# T1L_PHY.net
KiCad netlist of a schematic drawn in Altium Designer
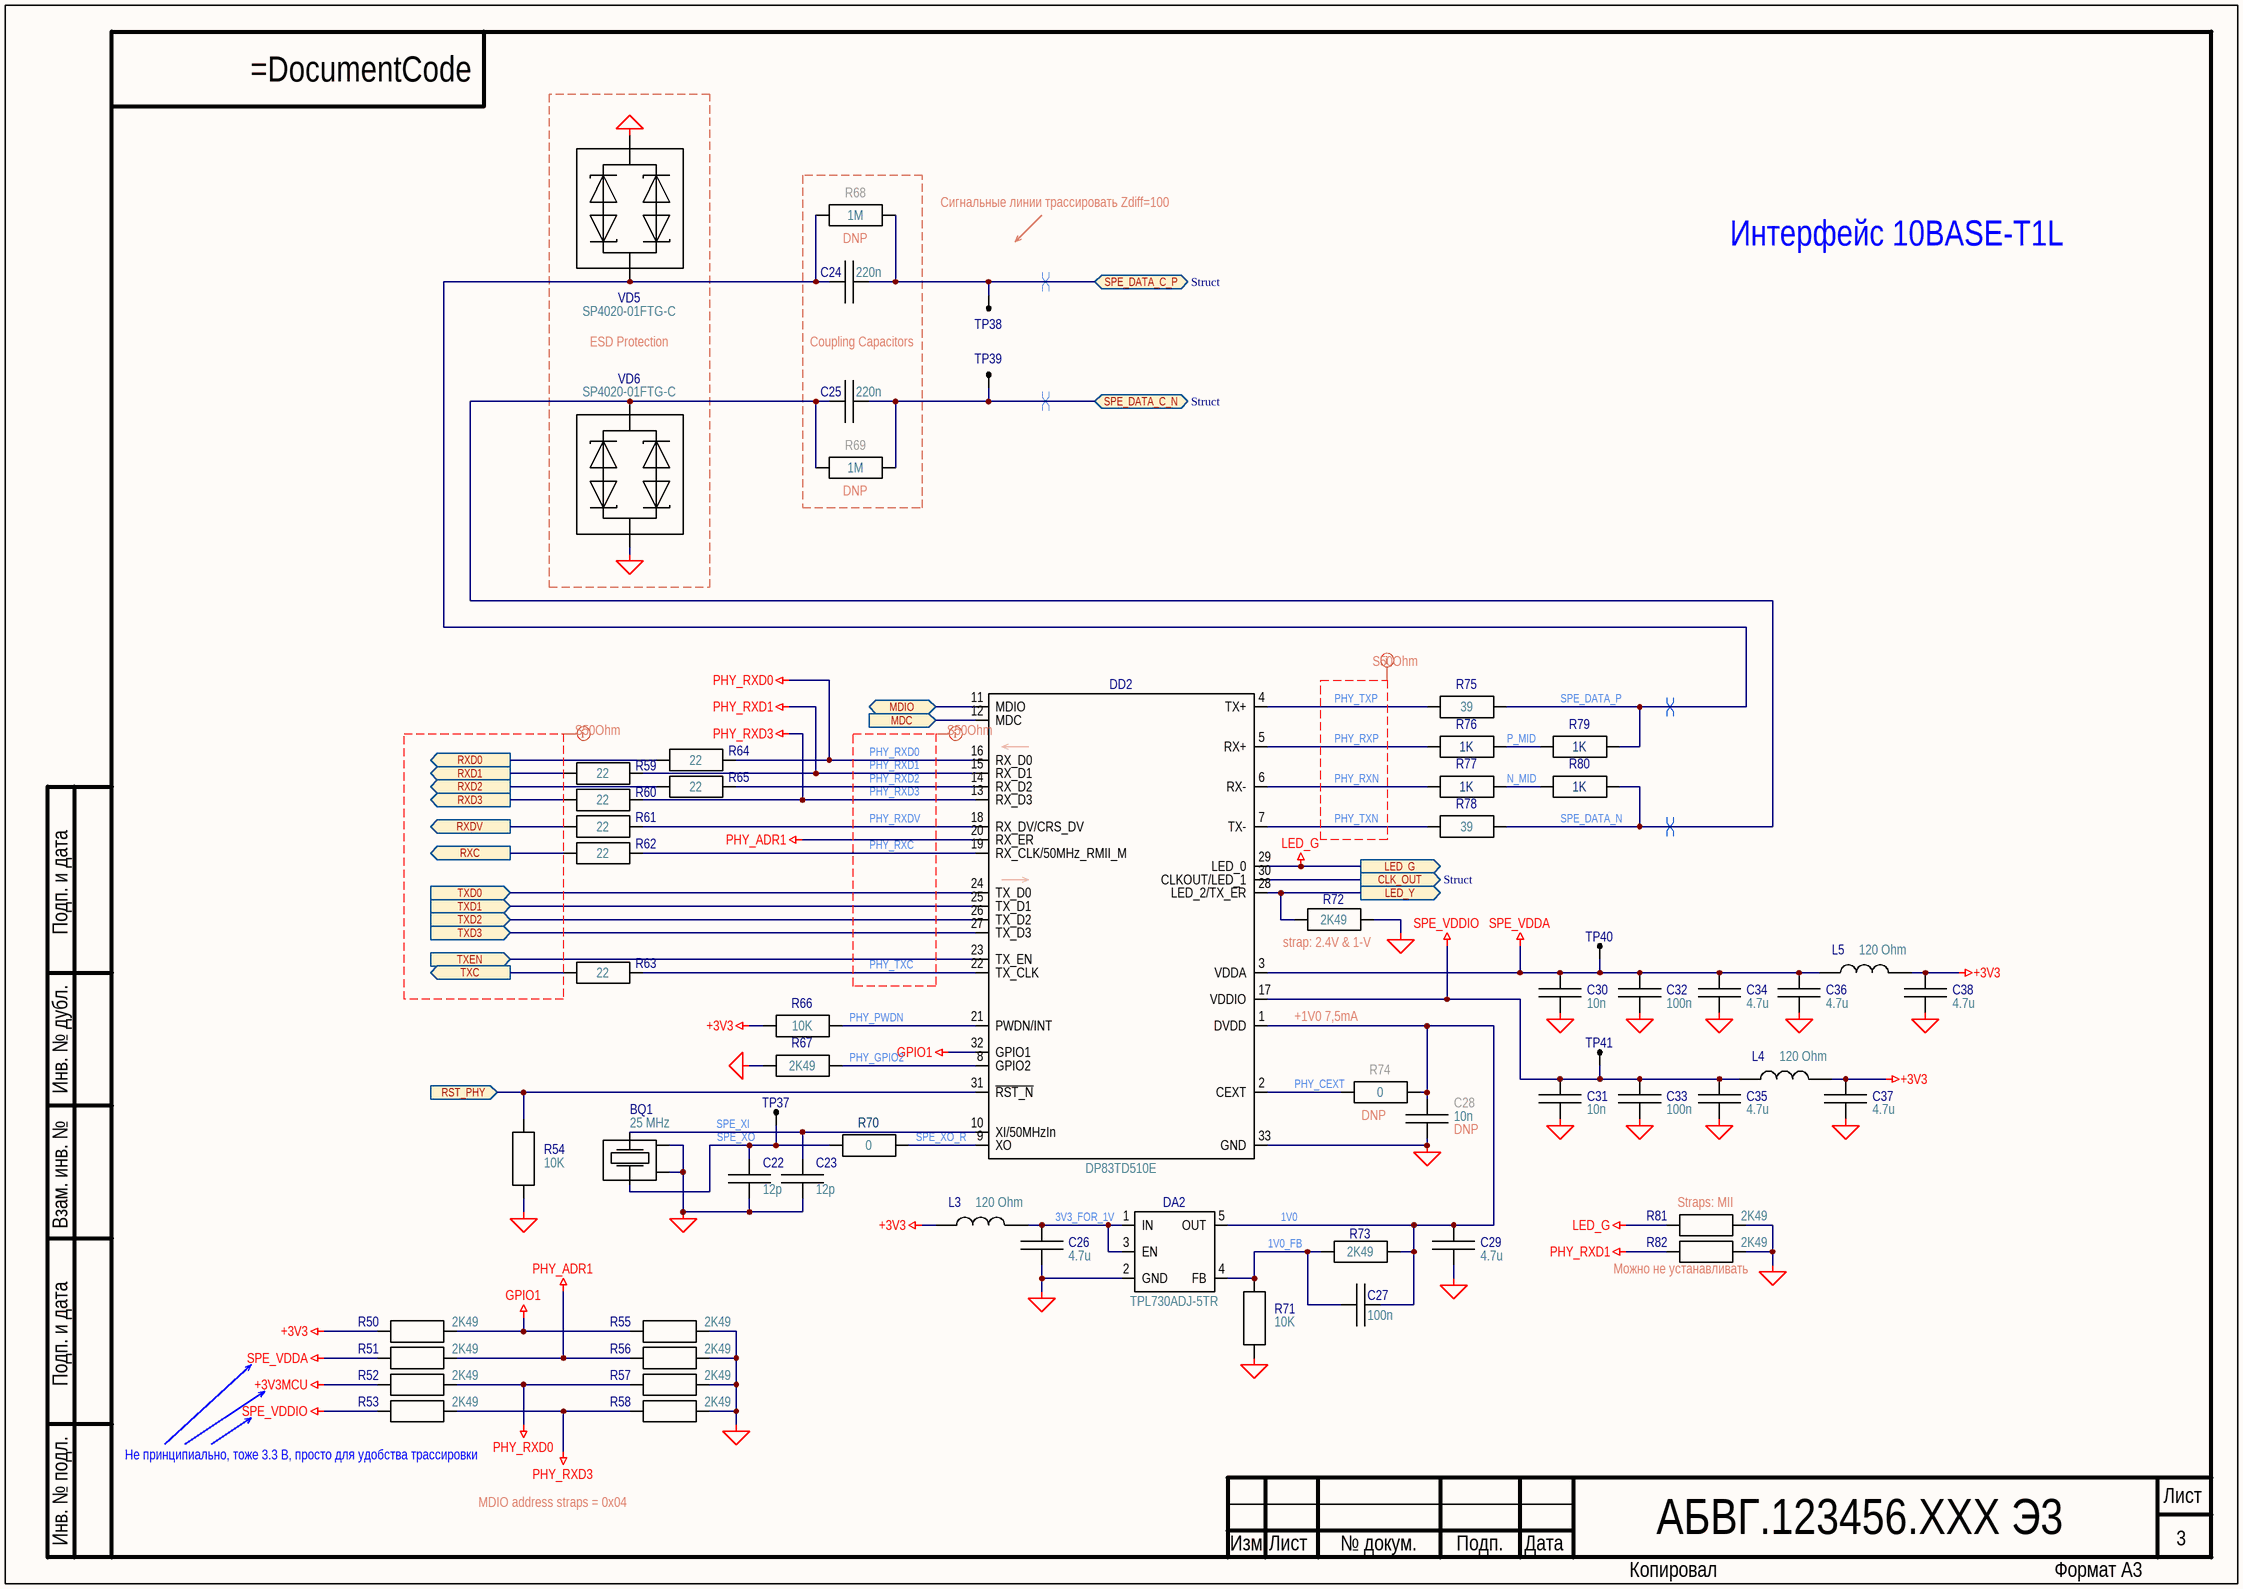
[diagram p0: T1L_PHY.SchDoc]

(export (version "E")
  (design (tool "Eeschema 10.0.6"))
  (components
    (comp (ref "BQ1")
      (value "25 MHz")
      (footprint "DSX321G_under12MHz")
      (description "Резонатор кварцевый X322525MOB4SI 25 MHz")
      (fields (field (name "MANUFACTURER PART NUMBER") "X322525MOB4SI") (field (name "MANUFACTURER") "YXC"))
      (libsource (lib "ums") (part "YSX321SL"))
    )
    (comp (ref "C22")
      (value "12p")
      (footprint "C0603")
      (description "Чип-конденсатор 12 пФ 5% 50 В C0G(NP0) 0603")
      (fields
        (field (name "MANUFACTURER PART NUMBER") "CC0603JRNPO9BN120")
        (field (name "MANUFACTURER") "Yageo")
      )
      (libsource (lib "ums") (part "C0603"))
    )
    (comp (ref "C23")
      (value "12p")
      (footprint "C0603")
      (description "Чип-конденсатор 12 пФ 5% 50 В C0G(NP0) 0603")
      (fields
        (field (name "MANUFACTURER PART NUMBER") "CC0603JRNPO9BN120")
        (field (name "MANUFACTURER") "Yageo")
      )
      (libsource (lib "ums") (part "C0603"))
    )
    (comp (ref "C24")
      (value "220n")
      (footprint "C0805_rounded")
      (description "Чип-конденсатор 0,22 мкФ ±10% 100 В X7R 0805")
      (fields
        (field (name "MANUFACTURER PART NUMBER") "CC0805KKX7R0BB224")
        (field (name "MANUFACTURER") "Yageo")
      )
      (libsource (lib "ums") (part "C0805_2"))
    )
    (comp (ref "C25")
      (value "220n")
      (footprint "C0805_rounded")
      (description "Чип-конденсатор 0,22 мкФ ±10% 100 В X7R 0805")
      (fields
        (field (name "MANUFACTURER PART NUMBER") "CC0805KKX7R0BB224")
        (field (name "MANUFACTURER") "Yageo")
      )
      (libsource (lib "ums") (part "C0805_2"))
    )
    (comp (ref "C26")
      (value "4.7u")
      (footprint "C0603")
      (description "Чип-конденсатор 4,7 мкФ 10% 16 В X5R 0603")
      (fields
        (field (name "MANUFACTURER PART NUMBER") "CC0603KRX5R7BB475")
        (field (name "MANUFACTURER") "Yageo")
      )
      (libsource (lib "ums") (part "C0603"))
    )
    (comp (ref "C27")
      (value "100n")
      (footprint "C0402")
      (description "Чип-конденсатор 100 нФ 10% 50 В X7R 0402")
      (fields
        (field (name "MANUFACTURER PART NUMBER") "CC0402KRX7R9BB104")
        (field (name "MANUFACTURER") "Yageo")
      )
      (libsource (lib "ums") (part "C0402"))
    )
    (comp (ref "C28")
      (value "10n")
      (footprint "C0402")
      (description "Чип-конденсатор 10 нФ 10% 50 В X7R 0402")
      (fields
        (field (name "MANUFACTURER PART NUMBER") "CC0402KRX7R9BB103")
        (field (name "MANUFACTURER") "Yageo")
      )
      (libsource (lib "ums") (part "C0402"))
    )
    (comp (ref "C29")
      (value "4.7u")
      (footprint "C0603")
      (description "Чип-конденсатор 4,7 мкФ 10% 16 В X5R 0603")
      (fields
        (field (name "MANUFACTURER PART NUMBER") "CC0603KRX5R7BB475")
        (field (name "MANUFACTURER") "Yageo")
      )
      (libsource (lib "ums") (part "C0603"))
    )
    (comp (ref "C30")
      (value "10n")
      (footprint "C0402")
      (description "Чип-конденсатор 10 нФ 10% 50 В X7R 0402")
      (fields
        (field (name "MANUFACTURER PART NUMBER") "CC0402KRX7R9BB103")
        (field (name "MANUFACTURER") "Yageo")
      )
      (libsource (lib "ums") (part "C0402"))
    )
    (comp (ref "C31")
      (value "10n")
      (footprint "C0402")
      (description "Чип-конденсатор 10 нФ 10% 50 В X7R 0402")
      (fields
        (field (name "MANUFACTURER PART NUMBER") "CC0402KRX7R9BB103")
        (field (name "MANUFACTURER") "Yageo")
      )
      (libsource (lib "ums") (part "C0402"))
    )
    (comp (ref "C32")
      (value "100n")
      (footprint "C0402")
      (description "Чип-конденсатор 100 нФ 10% 50 В X7R 0402")
      (fields
        (field (name "MANUFACTURER PART NUMBER") "CC0402KRX7R9BB104")
        (field (name "MANUFACTURER") "Yageo")
      )
      (libsource (lib "ums") (part "C0402"))
    )
    (comp (ref "C33")
      (value "100n")
      (footprint "C0402")
      (description "Чип-конденсатор 100 нФ 10% 50 В X7R 0402")
      (fields
        (field (name "MANUFACTURER PART NUMBER") "CC0402KRX7R9BB104")
        (field (name "MANUFACTURER") "Yageo")
      )
      (libsource (lib "ums") (part "C0402"))
    )
    (comp (ref "C34")
      (value "4.7u")
      (footprint "C0603")
      (description "Чип-конденсатор 4,7 мкФ 10% 16 В X5R 0603")
      (fields
        (field (name "MANUFACTURER PART NUMBER") "CC0603KRX5R7BB475")
        (field (name "MANUFACTURER") "Yageo")
      )
      (libsource (lib "ums") (part "C0603"))
    )
    (comp (ref "C35")
      (value "4.7u")
      (footprint "C0603")
      (description "Чип-конденсатор 4,7 мкФ 10% 16 В X5R 0603")
      (fields
        (field (name "MANUFACTURER PART NUMBER") "CC0603KRX5R7BB475")
        (field (name "MANUFACTURER") "Yageo")
      )
      (libsource (lib "ums") (part "C0603"))
    )
    (comp (ref "C36")
      (value "4.7u")
      (footprint "C0603")
      (description "Чип-конденсатор 4,7 мкФ 10% 16 В X5R 0603")
      (fields
        (field (name "MANUFACTURER PART NUMBER") "CC0603KRX5R7BB475")
        (field (name "MANUFACTURER") "Yageo")
      )
      (libsource (lib "ums") (part "C0603"))
    )
    (comp (ref "C37")
      (value "4.7u")
      (footprint "C0603")
      (description "Чип-конденсатор 4,7 мкФ 10% 16 В X5R 0603")
      (fields
        (field (name "MANUFACTURER PART NUMBER") "CC0603KRX5R7BB475")
        (field (name "MANUFACTURER") "Yageo")
      )
      (libsource (lib "ums") (part "C0603"))
    )
    (comp (ref "C38")
      (value "4.7u")
      (footprint "C0603")
      (description "Чип-конденсатор 4,7 мкФ 10% 16 В X5R 0603")
      (fields
        (field (name "MANUFACTURER PART NUMBER") "CC0603KRX5R7BB475")
        (field (name "MANUFACTURER") "Yageo")
      )
      (libsource (lib "ums") (part "C0603"))
    )
    (comp (ref "DA2")
      (value "TPL730ADJ-5TR")
      (footprint "SOT-23(DBV5)")
      (description "LDO-регулятор SOT-23-5")
      (fields (field (name "MANUFACTURER") "3PEAK"))
      (libsource (lib "ums") (part "TPL730ADJ-5TR"))
    )
    (comp (ref "DD2")
      (value "DP83TD510E")
      (footprint "QFN-32_ePAD_2.1x2.1")
      (description "Микросхема приёмопередатчика 10Base-T1L")
      (fields
        (field (name "MANUFACTURER") "Texas Instruments")
        (field (name "MANUFACTURER PART NUMBER") "DP83TD510ERHB")
      )
      (libsource (lib "ums") (part "DP83TD510E"))
    )
    (comp (ref "L3")
      (value "120 Ohm")
      (footprint "BLM18PG")
      (description "Фильтр индуктивный 120 Ом @ 100 МГц 2 А 0603")
      (fields
        (field (name "MANUFACTURER") "FENGHUA Advanced Technology")
        (field (name "MANUFACTURER PART NUMBER") "CBM160808U121T")
      )
      (libsource (lib "ums") (part "BLM18PG121SN1D"))
    )
    (comp (ref "L4")
      (value "120 Ohm")
      (footprint "BLM18PG")
      (description "Фильтр индуктивный 120 Ом @ 100 МГц 2 А 0603")
      (fields
        (field (name "MANUFACTURER") "FENGHUA Advanced Technology")
        (field (name "MANUFACTURER PART NUMBER") "CBM160808U121T")
      )
      (libsource (lib "ums") (part "BLM18PG121SN1D"))
    )
    (comp (ref "L5")
      (value "120 Ohm")
      (footprint "BLM18PG")
      (description "Фильтр индуктивный 120 Ом @ 100 МГц 2 А 0603")
      (fields
        (field (name "MANUFACTURER") "FENGHUA Advanced Technology")
        (field (name "MANUFACTURER PART NUMBER") "CBM160808U121T")
      )
      (libsource (lib "ums") (part "BLM18PG121SN1D"))
    )
    (comp (ref "R50")
      (value "2K49")
      (footprint "R0402")
      (description "Чип-резистор 2,49 кОм 1% 0402")
      (fields
        (field (name "MANUFACTURER PART NUMBER") "RC0402FR-072K49L")
        (field (name "MANUFACTURER") "Yageo")
      )
      (libsource (lib "ums") (part "R0402_tooth_4"))
    )
    (comp (ref "R51")
      (value "2K49")
      (footprint "R0402")
      (description "Чип-резистор 2,49 кОм 1% 0402")
      (fields
        (field (name "MANUFACTURER PART NUMBER") "RC0402FR-072K49L")
        (field (name "MANUFACTURER") "Yageo")
      )
      (libsource (lib "ums") (part "R0402_tooth_4"))
    )
    (comp (ref "R52")
      (value "2K49")
      (footprint "R0402")
      (description "Чип-резистор 2,49 кОм 1% 0402")
      (fields
        (field (name "MANUFACTURER PART NUMBER") "RC0402FR-072K49L")
        (field (name "MANUFACTURER") "Yageo")
      )
      (libsource (lib "ums") (part "R0402_tooth_4"))
    )
    (comp (ref "R53")
      (value "2K49")
      (footprint "R0402")
      (description "Чип-резистор 2,49 кОм 1% 0402")
      (fields
        (field (name "MANUFACTURER PART NUMBER") "RC0402FR-072K49L")
        (field (name "MANUFACTURER") "Yageo")
      )
      (libsource (lib "ums") (part "R0402_tooth_4"))
    )
    (comp (ref "R54")
      (value "10K")
      (footprint "R0402")
      (description "Чип-резистор 10 кОм 1% 0402")
      (fields
        (field (name "MANUFACTURER PART NUMBER") "RC0402FR-0710KL")
        (field (name "MANUFACTURER") "Yageo")
      )
      (libsource (lib "ums") (part "R0402"))
    )
    (comp (ref "R55")
      (value "2K49")
      (footprint "R0402")
      (description "Чип-резистор 2,49 кОм 1% 0402")
      (fields
        (field (name "MANUFACTURER PART NUMBER") "RC0402FR-072K49L")
        (field (name "MANUFACTURER") "Yageo")
      )
      (libsource (lib "ums") (part "R0402_tooth_4"))
    )
    (comp (ref "R56")
      (value "2K49")
      (footprint "R0402")
      (description "Чип-резистор 2,49 кОм 1% 0402")
      (fields
        (field (name "MANUFACTURER PART NUMBER") "RC0402FR-072K49L")
        (field (name "MANUFACTURER") "Yageo")
      )
      (libsource (lib "ums") (part "R0402_tooth_4"))
    )
    (comp (ref "R57")
      (value "2K49")
      (footprint "R0402")
      (description "Чип-резистор 2,49 кОм 1% 0402")
      (fields
        (field (name "MANUFACTURER PART NUMBER") "RC0402FR-072K49L")
        (field (name "MANUFACTURER") "Yageo")
      )
      (libsource (lib "ums") (part "R0402_tooth_4"))
    )
    (comp (ref "R58")
      (value "2K49")
      (footprint "R0402")
      (description "Чип-резистор 2,49 кОм 1% 0402")
      (fields
        (field (name "MANUFACTURER PART NUMBER") "RC0402FR-072K49L")
        (field (name "MANUFACTURER") "Yageo")
      )
      (libsource (lib "ums") (part "R0402_tooth_4"))
    )
    (comp (ref "R59")
      (value "22")
      (footprint "R0402")
      (description "Чип-резистор 22 Ом 1% 0402")
      (fields
        (field (name "MANUFACTURER PART NUMBER") "RC0402FR-0722RL")
        (field (name "MANUFACTURER") "Yageo")
      )
      (libsource (lib "ums") (part "R0402_tooth_1"))
    )
    (comp (ref "R60")
      (value "22")
      (footprint "R0402")
      (description "Чип-резистор 22 Ом 1% 0402")
      (fields
        (field (name "MANUFACTURER PART NUMBER") "RC0402FR-0722RL")
        (field (name "MANUFACTURER") "Yageo")
      )
      (libsource (lib "ums") (part "R0402_tooth_1"))
    )
    (comp (ref "R61")
      (value "22")
      (footprint "R0402")
      (description "Чип-резистор 22 Ом 1% 0402")
      (fields
        (field (name "MANUFACTURER PART NUMBER") "RC0402FR-0722RL")
        (field (name "MANUFACTURER") "Yageo")
      )
      (libsource (lib "ums") (part "R0402_tooth_1"))
    )
    (comp (ref "R62")
      (value "22")
      (footprint "R0402")
      (description "Чип-резистор 22 Ом 1% 0402")
      (fields
        (field (name "MANUFACTURER PART NUMBER") "RC0402FR-0722RL")
        (field (name "MANUFACTURER") "Yageo")
      )
      (libsource (lib "ums") (part "R0402_tooth_1"))
    )
    (comp (ref "R63")
      (value "22")
      (footprint "R0402")
      (description "Чип-резистор 22 Ом 1% 0402")
      (fields
        (field (name "MANUFACTURER PART NUMBER") "RC0402FR-0722RL")
        (field (name "MANUFACTURER") "Yageo")
      )
      (libsource (lib "ums") (part "R0402_tooth_1"))
    )
    (comp (ref "R64")
      (value "22")
      (footprint "R0402")
      (description "Чип-резистор 22 Ом 1% 0402")
      (fields
        (field (name "MANUFACTURER PART NUMBER") "RC0402FR-0722RL")
        (field (name "MANUFACTURER") "Yageo")
      )
      (libsource (lib "ums") (part "R0402_tooth_1"))
    )
    (comp (ref "R65")
      (value "22")
      (footprint "R0402")
      (description "Чип-резистор 22 Ом 1% 0402")
      (fields
        (field (name "MANUFACTURER PART NUMBER") "RC0402FR-0722RL")
        (field (name "MANUFACTURER") "Yageo")
      )
      (libsource (lib "ums") (part "R0402_tooth_1"))
    )
    (comp (ref "R66")
      (value "10K")
      (footprint "R0402")
      (description "Чип-резистор 10 кОм 1% 0402")
      (fields
        (field (name "MANUFACTURER PART NUMBER") "RC0402FR-0710KL")
        (field (name "MANUFACTURER") "Yageo")
      )
      (libsource (lib "ums") (part "R0402"))
    )
    (comp (ref "R67")
      (value "2K49")
      (footprint "R0402")
      (description "Чип-резистор 2,49 кОм 1% 0402")
      (fields
        (field (name "MANUFACTURER PART NUMBER") "RC0402FR-072K49L")
        (field (name "MANUFACTURER") "Yageo")
      )
      (libsource (lib "ums") (part "R0402"))
    )
    (comp (ref "R68")
      (value "1M")
      (footprint "R0603")
      (description "Чип-резистор 1 МОм 1% 0603")
      (fields
        (field (name "MANUFACTURER PART NUMBER") "RC0603FR-071ML")
        (field (name "MANUFACTURER") "Yageo")
      )
      (libsource (lib "ums") (part "R0603_13"))
    )
    (comp (ref "R69")
      (value "1M")
      (footprint "R0603")
      (description "Чип-резистор 1 МОм 1% 0603")
      (fields
        (field (name "MANUFACTURER PART NUMBER") "RC0603FR-071ML")
        (field (name "MANUFACTURER") "Yageo")
      )
      (libsource (lib "ums") (part "R0603_13"))
    )
    (comp (ref "R70")
      (value "0")
      (footprint "R0402")
      (description "Чип-резистор 0 ом 1% 0402")
      (fields
        (field (name "MANUFACTURER PART NUMBER") "RC0402FR-070RL")
        (field (name "MANUFACTURER") "Yageo")
      )
      (libsource (lib "ums") (part "R0402"))
    )
    (comp (ref "R71")
      (value "10K")
      (footprint "R0402")
      (description "Чип-резистор 10 кОм 1% 0402")
      (fields
        (field (name "MANUFACTURER PART NUMBER") "RC0402FR-0710KL")
        (field (name "MANUFACTURER") "Yageo")
      )
      (libsource (lib "ums") (part "R0402"))
    )
    (comp (ref "R72")
      (value "2K49")
      (footprint "R0402")
      (description "Чип-резистор 2,49 кОм 1% 0402")
      (fields
        (field (name "MANUFACTURER PART NUMBER") "RC0402FR-072K49L")
        (field (name "MANUFACTURER") "Yageo")
      )
      (libsource (lib "ums") (part "R0402"))
    )
    (comp (ref "R73")
      (value "2K49")
      (footprint "R0402")
      (description "Чип-резистор 2,49 кОм 1% 0402")
      (fields
        (field (name "MANUFACTURER PART NUMBER") "RC0402FR-072K49L")
        (field (name "MANUFACTURER") "Yageo")
      )
      (libsource (lib "ums") (part "R0402"))
    )
    (comp (ref "R74")
      (value "0")
      (footprint "R0402")
      (description "Чип-резистор 0 ом 1% 0402")
      (fields
        (field (name "MANUFACTURER PART NUMBER") "RC0402FR-070RL")
        (field (name "MANUFACTURER") "Yageo")
      )
      (libsource (lib "ums") (part "R0402"))
    )
    (comp (ref "R75")
      (value "39")
      (footprint "R0603")
      (description "Чип-резистор 39 Ом 1% 0603")
      (fields
        (field (name "MANUFACTURER PART NUMBER") "RC0603FR-0739RL")
        (field (name "MANUFACTURER") "Yageo")
      )
      (libsource (lib "ums") (part "R0603"))
    )
    (comp (ref "R76")
      (value "1K")
      (footprint "R0402")
      (description "Чип-резистор 1 кОм 1% 0402")
      (fields
        (field (name "MANUFACTURER PART NUMBER") "RC0402FR-071KL")
        (field (name "MANUFACTURER") "Yageo")
      )
      (libsource (lib "ums") (part "R0402_4"))
    )
    (comp (ref "R77")
      (value "1K")
      (footprint "R0402")
      (description "Чип-резистор 1 кОм 1% 0402")
      (fields
        (field (name "MANUFACTURER PART NUMBER") "RC0402FR-071KL")
        (field (name "MANUFACTURER") "Yageo")
      )
      (libsource (lib "ums") (part "R0402_4"))
    )
    (comp (ref "R78")
      (value "39")
      (footprint "R0603")
      (description "Чип-резистор 39 Ом 1% 0603")
      (fields
        (field (name "MANUFACTURER PART NUMBER") "RC0603FR-0739RL")
        (field (name "MANUFACTURER") "Yageo")
      )
      (libsource (lib "ums") (part "R0603"))
    )
    (comp (ref "R79")
      (value "1K")
      (footprint "R0402")
      (description "Чип-резистор 1 кОм 1% 0402")
      (fields
        (field (name "MANUFACTURER PART NUMBER") "RC0402FR-071KL")
        (field (name "MANUFACTURER") "Yageo")
      )
      (libsource (lib "ums") (part "R0402_4"))
    )
    (comp (ref "R80")
      (value "1K")
      (footprint "R0402")
      (description "Чип-резистор 1 кОм 1% 0402")
      (fields
        (field (name "MANUFACTURER PART NUMBER") "RC0402FR-071KL")
        (field (name "MANUFACTURER") "Yageo")
      )
      (libsource (lib "ums") (part "R0402_4"))
    )
    (comp (ref "R81")
      (value "2K49")
      (footprint "R0402")
      (description "Чип-резистор 2,49 кОм 1% 0402")
      (fields
        (field (name "MANUFACTURER PART NUMBER") "RC0402FR-072K49L")
        (field (name "MANUFACTURER") "Yageo")
      )
      (libsource (lib "ums") (part "R0402_tooth_4"))
    )
    (comp (ref "R82")
      (value "2K49")
      (footprint "R0402")
      (description "Чип-резистор 2,49 кОм 1% 0402")
      (fields
        (field (name "MANUFACTURER PART NUMBER") "RC0402FR-072K49L")
        (field (name "MANUFACTURER") "Yageo")
      )
      (libsource (lib "ums") (part "R0402_tooth_4"))
    )
    (comp (ref "TP37")
      (value "TEST_POINT_SMD")
      (footprint "TEST_POINT_SMD")
      (description "Контрольная точка SMD")
      (libsource (lib "ums") (part "TEST_POINT_SMD"))
    )
    (comp (ref "TP38")
      (value "TEST_POINT_1.27_STEP")
      (footprint "TEST_POINT_1.27_STEP")
      (description "Контрольная точка SMD")
      (libsource (lib "ums") (part "TEST_POINT_1.27_STEP"))
    )
    (comp (ref "TP39")
      (value "TEST_POINT_1.27_STEP")
      (footprint "TEST_POINT_1.27_STEP")
      (description "Контрольная точка SMD")
      (libsource (lib "ums") (part "TEST_POINT_1.27_STEP"))
    )
    (comp (ref "TP40")
      (value "TEST_POINT_SMD")
      (footprint "TEST_POINT_SMD")
      (description "Контрольная точка SMD")
      (libsource (lib "ums") (part "TEST_POINT_SMD"))
    )
    (comp (ref "TP41")
      (value "TEST_POINT_SMD")
      (footprint "TEST_POINT_SMD")
      (description "Контрольная точка SMD")
      (libsource (lib "ums") (part "TEST_POINT_SMD"))
    )
    (comp (ref "VD5")
      (value "SP4020-01FTG-C")
      (footprint "SOD-323_BI")
      (description "TVS-диод симметричный +3V3")
      (fields (field (name "MANUFACTURER") "TECH PUBLIC Co."))
      (libsource (lib "ums") (part "SP4020-01FTG-C"))
    )
    (comp (ref "VD6")
      (value "SP4020-01FTG-C")
      (footprint "SOD-323_BI")
      (description "TVS-диод симметричный +3V3")
      (fields (field (name "MANUFACTURER") "TECH PUBLIC Co."))
      (libsource (lib "ums") (part "SP4020-01FTG-C"))
    )
  )
  (nets
    (net (code "1") (name "+3V3") (class "Default")
      (node (ref "C37") (pin "1") (pinfunction "1_1") (pintype "passive"))
      (node (ref "C38") (pin "1") (pinfunction "1_1") (pintype "passive"))
      (node (ref "L3") (pin "1") (pinfunction "1_1") (pintype "passive"))
      (node (ref "L4") (pin "2") (pinfunction "2_2") (pintype "passive"))
      (node (ref "L5") (pin "2") (pinfunction "2_2") (pintype "passive"))
      (node (ref "R50") (pin "1") (pinfunction "1_1") (pintype "passive"))
      (node (ref "R66") (pin "1") (pinfunction "1_1") (pintype "passive"))
    )
    (net (code "2") (name "+3V3MCU") (class "Default")
      (node (ref "R52") (pin "1") (pinfunction "1_1") (pintype "passive"))
    )
    (net (code "3") (name "/1V0") (class "Default")
      (node (ref "C27") (pin "1") (pinfunction "1_1") (pintype "passive"))
      (node (ref "C28") (pin "2") (pinfunction "2_2") (pintype "passive"))
      (node (ref "C29") (pin "1") (pinfunction "1_1") (pintype "passive"))
      (node (ref "DA2") (pin "5") (pinfunction "OUT_5") (pintype "passive"))
      (node (ref "DD2") (pin "1") (pinfunction "DVDD_1") (pintype "passive"))
      (node (ref "R73") (pin "1") (pinfunction "1_1") (pintype "passive"))
      (node (ref "R74") (pin "2") (pinfunction "2_2") (pintype "passive"))
    )
    (net (code "4") (name "/1V0_FB") (class "Default")
      (node (ref "C27") (pin "2") (pinfunction "2_2") (pintype "passive"))
      (node (ref "DA2") (pin "4") (pinfunction "FB_4") (pintype "passive"))
      (node (ref "R71") (pin "2") (pinfunction "2_2") (pintype "passive"))
      (node (ref "R73") (pin "2") (pinfunction "2_2") (pintype "passive"))
    )
    (net (code "5") (name "/3V3_FOR_1V") (class "Default")
      (node (ref "C26") (pin "1") (pinfunction "1_1") (pintype "passive"))
      (node (ref "DA2") (pin "1") (pinfunction "IN_1") (pintype "passive"))
      (node (ref "DA2") (pin "3") (pinfunction "EN_3") (pintype "passive"))
      (node (ref "L3") (pin "2") (pinfunction "2_2") (pintype "passive"))
    )
    (net (code "7") (name "/CLK_OUT") (class "Default")
      (node (ref "DD2") (pin "30") (pinfunction "CLKOUT/LED_1_30") (pintype "passive"))
    )
    (net (code "8") (name "/LED_Y") (class "Default")
      (node (ref "DD2") (pin "28") (pinfunction "LED_2/TX_ER_28") (pintype "passive"))
      (node (ref "R72") (pin "1") (pinfunction "1_1") (pintype "passive"))
    )
    (net (code "9") (name "/MDC") (class "Default")
      (node (ref "DD2") (pin "12") (pinfunction "MDC_12") (pintype "passive"))
    )
    (net (code "10") (name "/MDIO") (class "Default")
      (node (ref "DD2") (pin "11") (pinfunction "MDIO_11") (pintype "passive"))
    )
    (net (code "11") (name "/N_MID") (class "Default")
      (node (ref "R77") (pin "2") (pinfunction "2_2") (pintype "passive"))
      (node (ref "R80") (pin "1") (pinfunction "1_1") (pintype "passive"))
    )
    (net (code "12") (name "/PHY_CEXT") (class "Default")
      (node (ref "DD2") (pin "2") (pinfunction "CEXT_2") (pintype "passive"))
      (node (ref "R74") (pin "1") (pinfunction "1_1") (pintype "passive"))
    )
    (net (code "13") (name "/PHY_GPIO2") (class "Default")
      (node (ref "DD2") (pin "8") (pinfunction "GPIO2_8") (pintype "passive"))
      (node (ref "R67") (pin "2") (pinfunction "2_2") (pintype "passive"))
    )
    (net (code "14") (name "/PHY_PWDN") (class "Default")
      (node (ref "DD2") (pin "21") (pinfunction "PWDN/INT_21") (pintype "passive"))
      (node (ref "R66") (pin "2") (pinfunction "2_2") (pintype "passive"))
    )
    (net (code "15") (name "/PHY_RXC") (class "Default")
      (node (ref "DD2") (pin "19") (pinfunction "RX_CLK/50MHz_RMII_M_19") (pintype "passive"))
      (node (ref "R62") (pin "2") (pinfunction "2_2") (pintype "passive"))
    )
    (net (code "16") (name "/PHY_RXD2") (class "Default")
      (node (ref "DD2") (pin "14") (pinfunction "RX_D2_14") (pintype "passive"))
      (node (ref "R65") (pin "2") (pinfunction "2_2") (pintype "passive"))
    )
    (net (code "17") (name "/PHY_RXDV") (class "Default")
      (node (ref "DD2") (pin "18") (pinfunction "RX_DV/CRS_DV_18") (pintype "passive"))
      (node (ref "R61") (pin "2") (pinfunction "2_2") (pintype "passive"))
    )
    (net (code "18") (name "/PHY_RXN") (class "Default")
      (node (ref "DD2") (pin "6") (pinfunction "RX-_6") (pintype "passive"))
      (node (ref "R77") (pin "1") (pinfunction "1_1") (pintype "passive"))
    )
    (net (code "19") (name "/PHY_RXP") (class "Default")
      (node (ref "DD2") (pin "5") (pinfunction "RX+_5") (pintype "passive"))
      (node (ref "R76") (pin "1") (pinfunction "1_1") (pintype "passive"))
    )
    (net (code "20") (name "/PHY_TXC") (class "Default")
      (node (ref "DD2") (pin "22") (pinfunction "TX_CLK_22") (pintype "passive"))
      (node (ref "R63") (pin "2") (pinfunction "2_2") (pintype "passive"))
    )
    (net (code "21") (name "/PHY_TXN") (class "Default")
      (node (ref "DD2") (pin "7") (pinfunction "TX-_7") (pintype "passive"))
      (node (ref "R78") (pin "1") (pinfunction "1_1") (pintype "passive"))
    )
    (net (code "22") (name "/PHY_TXP") (class "Default")
      (node (ref "DD2") (pin "4") (pinfunction "TX+_4") (pintype "passive"))
      (node (ref "R75") (pin "1") (pinfunction "1_1") (pintype "passive"))
    )
    (net (code "23") (name "/P_MID") (class "Default")
      (node (ref "R76") (pin "2") (pinfunction "2_2") (pintype "passive"))
      (node (ref "R79") (pin "1") (pinfunction "1_1") (pintype "passive"))
    )
    (net (code "24") (name "/RST_PHY") (class "Default")
      (node (ref "DD2") (pin "31") (pinfunction "~{RST_N}_31") (pintype "passive"))
      (node (ref "R54") (pin "2") (pinfunction "2_2") (pintype "passive"))
    )
    (net (code "25") (name "/RXC") (class "Default")
      (node (ref "R62") (pin "1") (pinfunction "1_1") (pintype "passive"))
    )
    (net (code "26") (name "/RXD0") (class "Default")
      (node (ref "R64") (pin "1") (pinfunction "1_1") (pintype "passive"))
    )
    (net (code "27") (name "/RXD1") (class "Default")
      (node (ref "R59") (pin "1") (pinfunction "1_1") (pintype "passive"))
    )
    (net (code "28") (name "/RXD2") (class "Default")
      (node (ref "R65") (pin "1") (pinfunction "1_1") (pintype "passive"))
    )
    (net (code "29") (name "/RXD3") (class "Default")
      (node (ref "R60") (pin "1") (pinfunction "1_1") (pintype "passive"))
    )
    (net (code "30") (name "/RXDV") (class "Default")
      (node (ref "R61") (pin "1") (pinfunction "1_1") (pintype "passive"))
    )
    (net (code "31") (name "/SPE_DATA_C_N") (class "Default")
      (node (ref "C25") (pin "2") (pinfunction "2_2") (pintype "passive"))
      (node (ref "R69") (pin "2") (pinfunction "2_2") (pintype "passive"))
      (node (ref "TP39") (pin "1") (pinfunction "1_1") (pintype "passive"))
    )
    (net (code "32") (name "/SPE_DATA_C_P") (class "Default")
      (node (ref "C24") (pin "2") (pinfunction "2_2") (pintype "passive"))
      (node (ref "R68") (pin "2") (pinfunction "2_2") (pintype "passive"))
      (node (ref "TP38") (pin "1") (pinfunction "1_1") (pintype "passive"))
    )
    (net (code "33") (name "/SPE_DATA_N") (class "Default")
      (node (ref "C25") (pin "1") (pinfunction "1_1") (pintype "passive"))
      (node (ref "R69") (pin "1") (pinfunction "1_1") (pintype "passive"))
      (node (ref "R78") (pin "2") (pinfunction "2_2") (pintype "passive"))
      (node (ref "R80") (pin "2") (pinfunction "2_2") (pintype "passive"))
      (node (ref "VD6") (pin "2") (pinfunction "2_2") (pintype "passive"))
    )
    (net (code "34") (name "/SPE_DATA_P") (class "Default")
      (node (ref "C24") (pin "1") (pinfunction "1_1") (pintype "passive"))
      (node (ref "R68") (pin "1") (pinfunction "1_1") (pintype "passive"))
      (node (ref "R75") (pin "2") (pinfunction "2_2") (pintype "passive"))
      (node (ref "R79") (pin "2") (pinfunction "2_2") (pintype "passive"))
      (node (ref "VD5") (pin "1") (pinfunction "1_1") (pintype "passive"))
    )
    (net (code "35") (name "/SPE_XI") (class "Default")
      (node (ref "BQ1") (pin "3") (pinfunction "3_3") (pintype "passive"))
      (node (ref "C23") (pin "1") (pinfunction "1_1") (pintype "passive"))
      (node (ref "DD2") (pin "10") (pinfunction "XI/50MHzIn_10") (pintype "passive"))
    )
    (net (code "36") (name "/SPE_XO") (class "Default")
      (node (ref "BQ1") (pin "1") (pinfunction "1_1") (pintype "passive"))
      (node (ref "C22") (pin "1") (pinfunction "1_1") (pintype "passive"))
      (node (ref "R70") (pin "1") (pinfunction "1_1") (pintype "passive"))
      (node (ref "TP37") (pin "1") (pinfunction "1_1") (pintype "passive"))
    )
    (net (code "37") (name "/SPE_XO_R") (class "Default")
      (node (ref "DD2") (pin "9") (pinfunction "XO_9") (pintype "passive"))
      (node (ref "R70") (pin "2") (pinfunction "2_2") (pintype "passive"))
    )
    (net (code "38") (name "/TXC") (class "Default")
      (node (ref "R63") (pin "1") (pinfunction "1_1") (pintype "passive"))
    )
    (net (code "39") (name "/TXD0") (class "Default")
      (node (ref "DD2") (pin "24") (pinfunction "TX_D0_24") (pintype "passive"))
    )
    (net (code "40") (name "/TXD1") (class "Default")
      (node (ref "DD2") (pin "25") (pinfunction "TX_D1_25") (pintype "passive"))
    )
    (net (code "41") (name "/TXD2") (class "Default")
      (node (ref "DD2") (pin "26") (pinfunction "TX_D2_26") (pintype "passive"))
    )
    (net (code "42") (name "/TXD3") (class "Default")
      (node (ref "DD2") (pin "27") (pinfunction "TX_D3_27") (pintype "passive"))
    )
    (net (code "43") (name "/TXEN") (class "Default")
      (node (ref "DD2") (pin "23") (pinfunction "TX_EN_23") (pintype "passive"))
    )
    (net (code "44") (name "GND") (class "Default")
      (node (ref "BQ1") (pin "2") (pinfunction "2_2") (pintype "passive"))
      (node (ref "BQ1") (pin "4") (pinfunction "4_4") (pintype "passive"))
      (node (ref "C22") (pin "2") (pinfunction "2_2") (pintype "passive"))
      (node (ref "C23") (pin "2") (pinfunction "2_2") (pintype "passive"))
      (node (ref "C26") (pin "2") (pinfunction "2_2") (pintype "passive"))
      (node (ref "C28") (pin "1") (pinfunction "1_1") (pintype "passive"))
      (node (ref "C29") (pin "2") (pinfunction "2_2") (pintype "passive"))
      (node (ref "C30") (pin "1") (pinfunction "1_1") (pintype "passive"))
      (node (ref "C31") (pin "1") (pinfunction "1_1") (pintype "passive"))
      (node (ref "C32") (pin "1") (pinfunction "1_1") (pintype "passive"))
      (node (ref "C33") (pin "1") (pinfunction "1_1") (pintype "passive"))
      (node (ref "C34") (pin "2") (pinfunction "2_2") (pintype "passive"))
      (node (ref "C35") (pin "2") (pinfunction "2_2") (pintype "passive"))
      (node (ref "C36") (pin "2") (pinfunction "2_2") (pintype "passive"))
      (node (ref "C37") (pin "2") (pinfunction "2_2") (pintype "passive"))
      (node (ref "C38") (pin "2") (pinfunction "2_2") (pintype "passive"))
      (node (ref "DA2") (pin "2") (pinfunction "GND_2") (pintype "passive"))
      (node (ref "DD2") (pin "33") (pinfunction "GND_33") (pintype "passive"))
      (node (ref "R54") (pin "1") (pinfunction "1_1") (pintype "passive"))
      (node (ref "R55") (pin "2") (pinfunction "2_2") (pintype "passive"))
      (node (ref "R56") (pin "2") (pinfunction "2_2") (pintype "passive"))
      (node (ref "R57") (pin "2") (pinfunction "2_2") (pintype "passive"))
      (node (ref "R58") (pin "2") (pinfunction "2_2") (pintype "passive"))
      (node (ref "R67") (pin "1") (pinfunction "1_1") (pintype "passive"))
      (node (ref "R71") (pin "1") (pinfunction "1_1") (pintype "passive"))
      (node (ref "R72") (pin "2") (pinfunction "2_2") (pintype "passive"))
      (node (ref "R81") (pin "2") (pinfunction "2_2") (pintype "passive"))
      (node (ref "R82") (pin "2") (pinfunction "2_2") (pintype "passive"))
      (node (ref "VD5") (pin "2") (pinfunction "2_2") (pintype "passive"))
      (node (ref "VD6") (pin "1") (pinfunction "1_1") (pintype "passive"))
    )
    (net (code "45") (name "GPIO1") (class "Default")
      (node (ref "DD2") (pin "32") (pinfunction "GPIO1_32") (pintype "passive"))
      (node (ref "R50") (pin "2") (pinfunction "2_2") (pintype "passive"))
      (node (ref "R55") (pin "1") (pinfunction "1_1") (pintype "passive"))
    )
    (net (code "46") (name "LED_G") (class "Default")
      (node (ref "DD2") (pin "29") (pinfunction "LED_0_29") (pintype "passive"))
      (node (ref "R81") (pin "1") (pinfunction "1_1") (pintype "passive"))
    )
    (net (code "47") (name "PHY_ADR1") (class "Default")
      (node (ref "DD2") (pin "20") (pinfunction "RX_ER_20") (pintype "passive"))
      (node (ref "R51") (pin "2") (pinfunction "2_2") (pintype "passive"))
      (node (ref "R56") (pin "1") (pinfunction "1_1") (pintype "passive"))
    )
    (net (code "48") (name "PHY_RXD0") (class "Default")
      (node (ref "DD2") (pin "16") (pinfunction "RX_D0_16") (pintype "passive"))
      (node (ref "R52") (pin "2") (pinfunction "2_2") (pintype "passive"))
      (node (ref "R57") (pin "1") (pinfunction "1_1") (pintype "passive"))
      (node (ref "R64") (pin "2") (pinfunction "2_2") (pintype "passive"))
    )
    (net (code "49") (name "PHY_RXD1") (class "Default")
      (node (ref "DD2") (pin "15") (pinfunction "RX_D1_15") (pintype "passive"))
      (node (ref "R59") (pin "2") (pinfunction "2_2") (pintype "passive"))
      (node (ref "R82") (pin "1") (pinfunction "1_1") (pintype "passive"))
    )
    (net (code "50") (name "PHY_RXD3") (class "Default")
      (node (ref "DD2") (pin "13") (pinfunction "RX_D3_13") (pintype "passive"))
      (node (ref "R53") (pin "2") (pinfunction "2_2") (pintype "passive"))
      (node (ref "R58") (pin "1") (pinfunction "1_1") (pintype "passive"))
      (node (ref "R60") (pin "2") (pinfunction "2_2") (pintype "passive"))
    )
    (net (code "51") (name "SPE_VDDA") (class "Default")
      (node (ref "C30") (pin "2") (pinfunction "2_2") (pintype "passive"))
      (node (ref "C32") (pin "2") (pinfunction "2_2") (pintype "passive"))
      (node (ref "C34") (pin "1") (pinfunction "1_1") (pintype "passive"))
      (node (ref "C36") (pin "1") (pinfunction "1_1") (pintype "passive"))
      (node (ref "DD2") (pin "3") (pinfunction "VDDA_3") (pintype "passive"))
      (node (ref "L5") (pin "1") (pinfunction "1_1") (pintype "passive"))
      (node (ref "R51") (pin "1") (pinfunction "1_1") (pintype "passive"))
      (node (ref "TP40") (pin "1") (pinfunction "1_1") (pintype "passive"))
    )
    (net (code "52") (name "SPE_VDDIO") (class "Default")
      (node (ref "C31") (pin "2") (pinfunction "2_2") (pintype "passive"))
      (node (ref "C33") (pin "2") (pinfunction "2_2") (pintype "passive"))
      (node (ref "C35") (pin "1") (pinfunction "1_1") (pintype "passive"))
      (node (ref "DD2") (pin "17") (pinfunction "VDDIO_17") (pintype "passive"))
      (node (ref "L4") (pin "1") (pinfunction "1_1") (pintype "passive"))
      (node (ref "R53") (pin "1") (pinfunction "1_1") (pintype "passive"))
      (node (ref "TP41") (pin "1") (pinfunction "1_1") (pintype "passive"))
    )
  )
)
